# sensors.net
KiCad netlist of a schematic drawn in Altium Designer
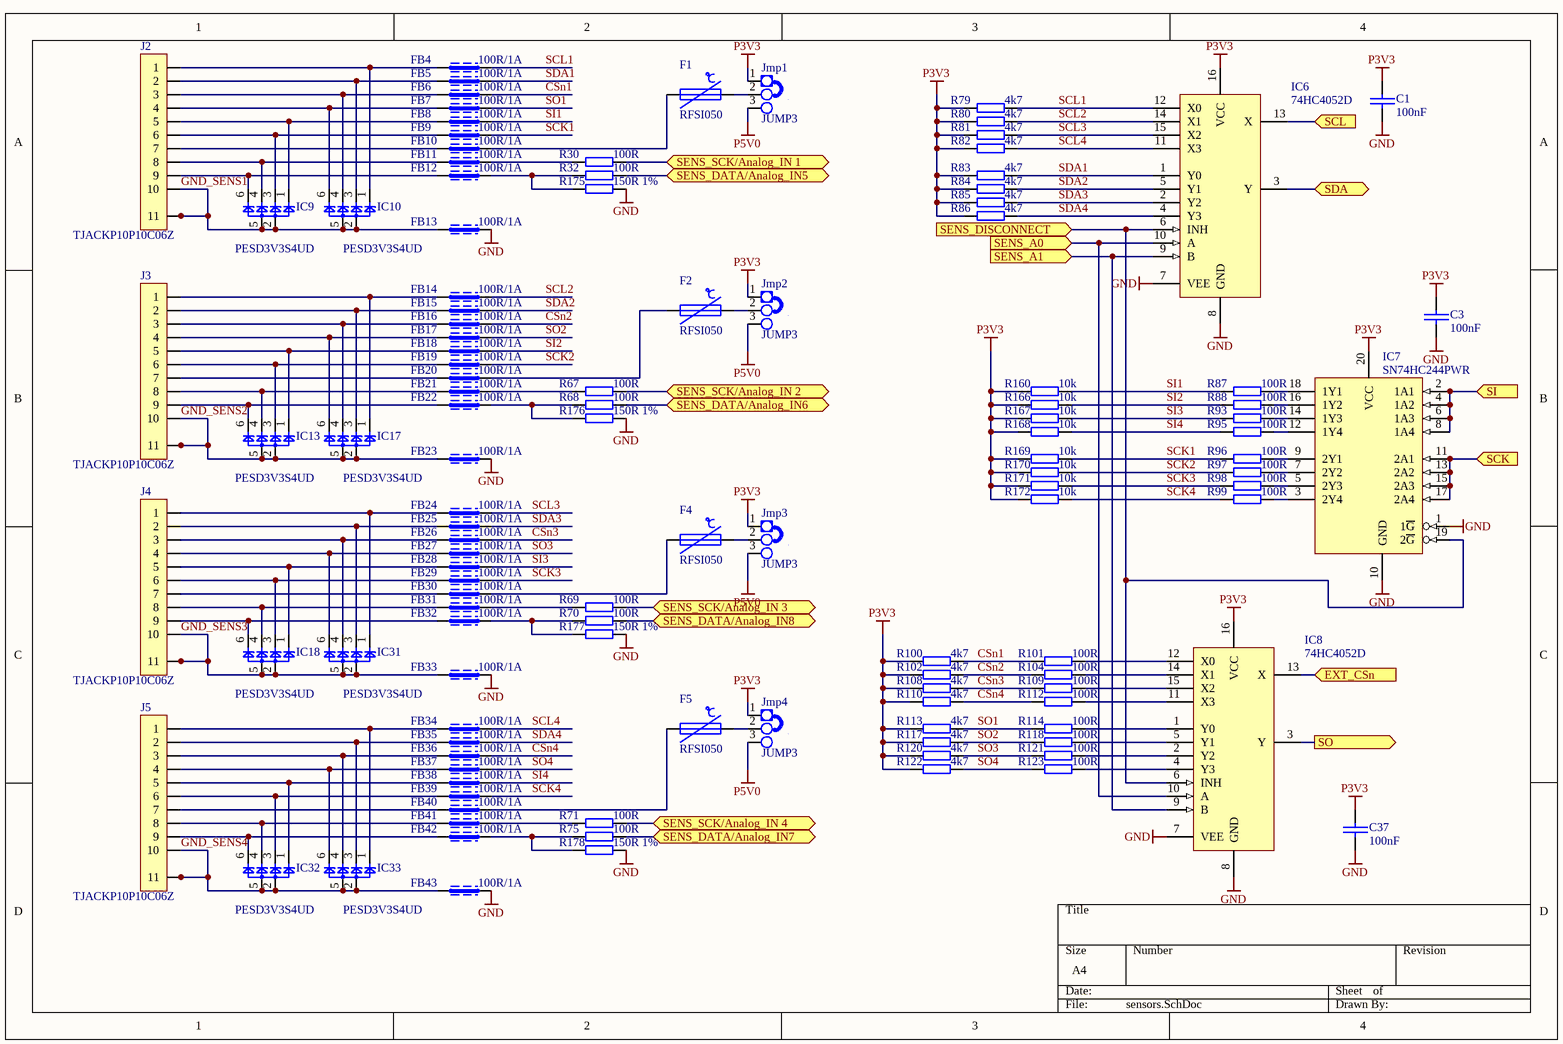
[diagram p0: sensors.SchDoc]

(export (version "E")
  (design (tool "Eeschema 10.0.6"))
  (components
    (comp (ref "C1")
      (value "100nF")
      (footprint "0402C")
      (description "Capacitor SMD")
      (libsource (lib "LIBRARY_SCH") (part "CAP_SMD_0402"))
    )
    (comp (ref "C3")
      (value "100nF")
      (footprint "0402C")
      (description "Capacitor SMD")
      (libsource (lib "LIBRARY_SCH") (part "CAP_SMD_0402"))
    )
    (comp (ref "C37")
      (value "100nF")
      (footprint "0402C")
      (description "Capacitor SMD")
      (libsource (lib "LIBRARY_SCH") (part "CAP_SMD_0402"))
    )
    (comp (ref "F1")
      (value "RFSI050")
      (footprint "0805R")
      (description "50mA polymer FUSE")
      (libsource (lib "LIBRARY_SCH") (part "F_PTC_0.05A"))
    )
    (comp (ref "F2")
      (value "RFSI050")
      (footprint "0805R")
      (description "50mA polymer FUSE")
      (libsource (lib "LIBRARY_SCH") (part "F_PTC_0.05A"))
    )
    (comp (ref "F4")
      (value "RFSI050")
      (footprint "0805R")
      (description "50mA polymer FUSE")
      (libsource (lib "LIBRARY_SCH") (part "F_PTC_0.05A"))
    )
    (comp (ref "F5")
      (value "RFSI050")
      (footprint "0805R")
      (description "50mA polymer FUSE")
      (libsource (lib "LIBRARY_SCH") (part "F_PTC_0.05A"))
    )
    (comp (ref "FB4")
      (value "100R/1A")
      (footprint "0603L")
      (description "ferrite bead 100R@100MHz 1A")
      (libsource (lib "LIBRARY_SCH") (part "L_FERRITE_BEAD_0603"))
    )
    (comp (ref "FB5")
      (value "100R/1A")
      (footprint "0603L")
      (description "ferrite bead 100R@100MHz 1A")
      (libsource (lib "LIBRARY_SCH") (part "L_FERRITE_BEAD_0603"))
    )
    (comp (ref "FB6")
      (value "100R/1A")
      (footprint "0603L")
      (description "ferrite bead 100R@100MHz 1A")
      (libsource (lib "LIBRARY_SCH") (part "L_FERRITE_BEAD_0603"))
    )
    (comp (ref "FB7")
      (value "100R/1A")
      (footprint "0603L")
      (description "ferrite bead 100R@100MHz 1A")
      (libsource (lib "LIBRARY_SCH") (part "L_FERRITE_BEAD_0603"))
    )
    (comp (ref "FB8")
      (value "100R/1A")
      (footprint "0603L")
      (description "ferrite bead 100R@100MHz 1A")
      (libsource (lib "LIBRARY_SCH") (part "L_FERRITE_BEAD_0603"))
    )
    (comp (ref "FB9")
      (value "100R/1A")
      (footprint "0603L")
      (description "ferrite bead 100R@100MHz 1A")
      (libsource (lib "LIBRARY_SCH") (part "L_FERRITE_BEAD_0603"))
    )
    (comp (ref "FB10")
      (value "100R/1A")
      (footprint "0603L")
      (description "ferrite bead 100R@100MHz 1A")
      (libsource (lib "LIBRARY_SCH") (part "L_FERRITE_BEAD_0603"))
    )
    (comp (ref "FB11")
      (value "100R/1A")
      (footprint "0603L")
      (description "ferrite bead 100R@100MHz 1A")
      (libsource (lib "LIBRARY_SCH") (part "L_FERRITE_BEAD_0603"))
    )
    (comp (ref "FB12")
      (value "100R/1A")
      (footprint "0603L")
      (description "ferrite bead 100R@100MHz 1A")
      (libsource (lib "LIBRARY_SCH") (part "L_FERRITE_BEAD_0603"))
    )
    (comp (ref "FB13")
      (value "100R/1A")
      (footprint "0603L")
      (description "ferrite bead 100R@100MHz 1A")
      (libsource (lib "LIBRARY_SCH") (part "L_FERRITE_BEAD_0603"))
    )
    (comp (ref "FB14")
      (value "100R/1A")
      (footprint "0603L")
      (description "ferrite bead 100R@100MHz 1A")
      (libsource (lib "LIBRARY_SCH") (part "L_FERRITE_BEAD_0603"))
    )
    (comp (ref "FB15")
      (value "100R/1A")
      (footprint "0603L")
      (description "ferrite bead 100R@100MHz 1A")
      (libsource (lib "LIBRARY_SCH") (part "L_FERRITE_BEAD_0603"))
    )
    (comp (ref "FB16")
      (value "100R/1A")
      (footprint "0603L")
      (description "ferrite bead 100R@100MHz 1A")
      (libsource (lib "LIBRARY_SCH") (part "L_FERRITE_BEAD_0603"))
    )
    (comp (ref "FB17")
      (value "100R/1A")
      (footprint "0603L")
      (description "ferrite bead 100R@100MHz 1A")
      (libsource (lib "LIBRARY_SCH") (part "L_FERRITE_BEAD_0603"))
    )
    (comp (ref "FB18")
      (value "100R/1A")
      (footprint "0603L")
      (description "ferrite bead 100R@100MHz 1A")
      (libsource (lib "LIBRARY_SCH") (part "L_FERRITE_BEAD_0603"))
    )
    (comp (ref "FB19")
      (value "100R/1A")
      (footprint "0603L")
      (description "ferrite bead 100R@100MHz 1A")
      (libsource (lib "LIBRARY_SCH") (part "L_FERRITE_BEAD_0603"))
    )
    (comp (ref "FB20")
      (value "100R/1A")
      (footprint "0603L")
      (description "ferrite bead 100R@100MHz 1A")
      (libsource (lib "LIBRARY_SCH") (part "L_FERRITE_BEAD_0603"))
    )
    (comp (ref "FB21")
      (value "100R/1A")
      (footprint "0603L")
      (description "ferrite bead 100R@100MHz 1A")
      (libsource (lib "LIBRARY_SCH") (part "L_FERRITE_BEAD_0603"))
    )
    (comp (ref "FB22")
      (value "100R/1A")
      (footprint "0603L")
      (description "ferrite bead 100R@100MHz 1A")
      (libsource (lib "LIBRARY_SCH") (part "L_FERRITE_BEAD_0603"))
    )
    (comp (ref "FB23")
      (value "100R/1A")
      (footprint "0603L")
      (description "ferrite bead 100R@100MHz 1A")
      (libsource (lib "LIBRARY_SCH") (part "L_FERRITE_BEAD_0603"))
    )
    (comp (ref "FB24")
      (value "100R/1A")
      (footprint "0603L")
      (description "ferrite bead 100R@100MHz 1A")
      (libsource (lib "LIBRARY_SCH") (part "L_FERRITE_BEAD_0603"))
    )
    (comp (ref "FB25")
      (value "100R/1A")
      (footprint "0603L")
      (description "ferrite bead 100R@100MHz 1A")
      (libsource (lib "LIBRARY_SCH") (part "L_FERRITE_BEAD_0603"))
    )
    (comp (ref "FB26")
      (value "100R/1A")
      (footprint "0603L")
      (description "ferrite bead 100R@100MHz 1A")
      (libsource (lib "LIBRARY_SCH") (part "L_FERRITE_BEAD_0603"))
    )
    (comp (ref "FB27")
      (value "100R/1A")
      (footprint "0603L")
      (description "ferrite bead 100R@100MHz 1A")
      (libsource (lib "LIBRARY_SCH") (part "L_FERRITE_BEAD_0603"))
    )
    (comp (ref "FB28")
      (value "100R/1A")
      (footprint "0603L")
      (description "ferrite bead 100R@100MHz 1A")
      (libsource (lib "LIBRARY_SCH") (part "L_FERRITE_BEAD_0603"))
    )
    (comp (ref "FB29")
      (value "100R/1A")
      (footprint "0603L")
      (description "ferrite bead 100R@100MHz 1A")
      (libsource (lib "LIBRARY_SCH") (part "L_FERRITE_BEAD_0603"))
    )
    (comp (ref "FB30")
      (value "100R/1A")
      (footprint "0603L")
      (description "ferrite bead 100R@100MHz 1A")
      (libsource (lib "LIBRARY_SCH") (part "L_FERRITE_BEAD_0603"))
    )
    (comp (ref "FB31")
      (value "100R/1A")
      (footprint "0603L")
      (description "ferrite bead 100R@100MHz 1A")
      (libsource (lib "LIBRARY_SCH") (part "L_FERRITE_BEAD_0603"))
    )
    (comp (ref "FB32")
      (value "100R/1A")
      (footprint "0603L")
      (description "ferrite bead 100R@100MHz 1A")
      (libsource (lib "LIBRARY_SCH") (part "L_FERRITE_BEAD_0603"))
    )
    (comp (ref "FB33")
      (value "100R/1A")
      (footprint "0603L")
      (description "ferrite bead 100R@100MHz 1A")
      (libsource (lib "LIBRARY_SCH") (part "L_FERRITE_BEAD_0603"))
    )
    (comp (ref "FB34")
      (value "100R/1A")
      (footprint "0603L")
      (description "ferrite bead 100R@100MHz 1A")
      (libsource (lib "LIBRARY_SCH") (part "L_FERRITE_BEAD_0603"))
    )
    (comp (ref "FB35")
      (value "100R/1A")
      (footprint "0603L")
      (description "ferrite bead 100R@100MHz 1A")
      (libsource (lib "LIBRARY_SCH") (part "L_FERRITE_BEAD_0603"))
    )
    (comp (ref "FB36")
      (value "100R/1A")
      (footprint "0603L")
      (description "ferrite bead 100R@100MHz 1A")
      (libsource (lib "LIBRARY_SCH") (part "L_FERRITE_BEAD_0603"))
    )
    (comp (ref "FB37")
      (value "100R/1A")
      (footprint "0603L")
      (description "ferrite bead 100R@100MHz 1A")
      (libsource (lib "LIBRARY_SCH") (part "L_FERRITE_BEAD_0603"))
    )
    (comp (ref "FB38")
      (value "100R/1A")
      (footprint "0603L")
      (description "ferrite bead 100R@100MHz 1A")
      (libsource (lib "LIBRARY_SCH") (part "L_FERRITE_BEAD_0603"))
    )
    (comp (ref "FB39")
      (value "100R/1A")
      (footprint "0603L")
      (description "ferrite bead 100R@100MHz 1A")
      (libsource (lib "LIBRARY_SCH") (part "L_FERRITE_BEAD_0603"))
    )
    (comp (ref "FB40")
      (value "100R/1A")
      (footprint "0603L")
      (description "ferrite bead 100R@100MHz 1A")
      (libsource (lib "LIBRARY_SCH") (part "L_FERRITE_BEAD_0603"))
    )
    (comp (ref "FB41")
      (value "100R/1A")
      (footprint "0603L")
      (description "ferrite bead 100R@100MHz 1A")
      (libsource (lib "LIBRARY_SCH") (part "L_FERRITE_BEAD_0603"))
    )
    (comp (ref "FB42")
      (value "100R/1A")
      (footprint "0603L")
      (description "ferrite bead 100R@100MHz 1A")
      (libsource (lib "LIBRARY_SCH") (part "L_FERRITE_BEAD_0603"))
    )
    (comp (ref "FB43")
      (value "100R/1A")
      (footprint "0603L")
      (description "ferrite bead 100R@100MHz 1A")
      (libsource (lib "LIBRARY_SCH") (part "L_FERRITE_BEAD_0603"))
    )
    (comp (ref "IC6") (value "74HC4052D") (footprint "SO-16") (libsource (lib "LIBRARY_SCH") (part "4052")))
    (comp (ref "IC7")
      (value "SN74HC244PWR")
      (footprint "tssop20")
      (description "TTL BUS tristate")
      (libsource (lib "LIBRARY_SCH") (part "74HC244"))
    )
    (comp (ref "IC8") (value "74HC4052D") (footprint "SO-16") (libsource (lib "LIBRARY_SCH") (part "4052")))
    (comp (ref "IC9")
      (value "PESD3V3S4UD")
      (footprint "SOT457")
      (description "3.3V TVS")
      (libsource (lib "LIBRARY_SCH") (part "D_TVS_PESD3V3S4UD"))
    )
    (comp (ref "IC10")
      (value "PESD3V3S4UD")
      (footprint "SOT457")
      (description "3.3V TVS")
      (libsource (lib "LIBRARY_SCH") (part "D_TVS_PESD3V3S4UD"))
    )
    (comp (ref "IC13")
      (value "PESD3V3S4UD")
      (footprint "SOT457")
      (description "3.3V TVS")
      (libsource (lib "LIBRARY_SCH") (part "D_TVS_PESD3V3S4UD"))
    )
    (comp (ref "IC17")
      (value "PESD3V3S4UD")
      (footprint "SOT457")
      (description "3.3V TVS")
      (libsource (lib "LIBRARY_SCH") (part "D_TVS_PESD3V3S4UD"))
    )
    (comp (ref "IC18")
      (value "PESD3V3S4UD")
      (footprint "SOT457")
      (description "3.3V TVS")
      (libsource (lib "LIBRARY_SCH") (part "D_TVS_PESD3V3S4UD"))
    )
    (comp (ref "IC31")
      (value "PESD3V3S4UD")
      (footprint "SOT457")
      (description "3.3V TVS")
      (libsource (lib "LIBRARY_SCH") (part "D_TVS_PESD3V3S4UD"))
    )
    (comp (ref "IC32")
      (value "PESD3V3S4UD")
      (footprint "SOT457")
      (description "3.3V TVS")
      (libsource (lib "LIBRARY_SCH") (part "D_TVS_PESD3V3S4UD"))
    )
    (comp (ref "IC33")
      (value "PESD3V3S4UD")
      (footprint "SOT457")
      (description "3.3V TVS")
      (libsource (lib "LIBRARY_SCH") (part "D_TVS_PESD3V3S4UD"))
    )
    (comp (ref "J2")
      (value "TJACKP10P10C06Z")
      (footprint "TJACKP10P10C06Z")
      (description "Modular 10pin (Maritex or Molex)")
      (libsource (lib "LIBRARY_SCH") (part "CON_MOD_10pin_V"))
    )
    (comp (ref "J3")
      (value "TJACKP10P10C06Z")
      (footprint "TJACKP10P10C06Z")
      (description "Modular 10pin (Maritex or Molex)")
      (libsource (lib "LIBRARY_SCH") (part "CON_MOD_10pin_V"))
    )
    (comp (ref "J4")
      (value "TJACKP10P10C06Z")
      (footprint "TJACKP10P10C06Z")
      (description "Modular 10pin (Maritex or Molex)")
      (libsource (lib "LIBRARY_SCH") (part "CON_MOD_10pin_V"))
    )
    (comp (ref "J5")
      (value "TJACKP10P10C06Z")
      (footprint "TJACKP10P10C06Z")
      (description "Modular 10pin (Maritex or Molex)")
      (libsource (lib "LIBRARY_SCH") (part "CON_MOD_10pin_V"))
    )
    (comp (ref "Jmp1") (value "JUMP3") (footprint "jump3") (libsource (lib "LIBRARY_SCH") (part "JUMP3")))
    (comp (ref "Jmp2") (value "JUMP3") (footprint "jump3") (libsource (lib "LIBRARY_SCH") (part "JUMP3")))
    (comp (ref "Jmp3") (value "JUMP3") (footprint "jump3") (libsource (lib "LIBRARY_SCH") (part "JUMP3")))
    (comp (ref "Jmp4") (value "JUMP3") (footprint "jump3") (libsource (lib "LIBRARY_SCH") (part "JUMP3")))
    (comp (ref "R30")
      (value "100R")
      (footprint "0402R")
      (description "SMD Resistor")
      (libsource (lib "LIBRARY_SCH") (part "RES_0402"))
    )
    (comp (ref "R32")
      (value "100R")
      (footprint "0402R")
      (description "SMD Resistor")
      (libsource (lib "LIBRARY_SCH") (part "RES_0402"))
    )
    (comp (ref "R67")
      (value "100R")
      (footprint "0402R")
      (description "SMD Resistor")
      (libsource (lib "LIBRARY_SCH") (part "RES_0402"))
    )
    (comp (ref "R68")
      (value "100R")
      (footprint "0402R")
      (description "SMD Resistor")
      (libsource (lib "LIBRARY_SCH") (part "RES_0402"))
    )
    (comp (ref "R69")
      (value "100R")
      (footprint "0402R")
      (description "SMD Resistor")
      (libsource (lib "LIBRARY_SCH") (part "RES_0402"))
    )
    (comp (ref "R70")
      (value "100R")
      (footprint "0402R")
      (description "SMD Resistor")
      (libsource (lib "LIBRARY_SCH") (part "RES_0402"))
    )
    (comp (ref "R71")
      (value "100R")
      (footprint "0402R")
      (description "SMD Resistor")
      (libsource (lib "LIBRARY_SCH") (part "RES_0402"))
    )
    (comp (ref "R75")
      (value "100R")
      (footprint "0402R")
      (description "SMD Resistor")
      (libsource (lib "LIBRARY_SCH") (part "RES_0402"))
    )
    (comp (ref "R79")
      (value "4k7")
      (footprint "0402R")
      (description "SMD Resistor")
      (libsource (lib "LIBRARY_SCH") (part "RES_0402"))
    )
    (comp (ref "R80")
      (value "4k7")
      (footprint "0402R")
      (description "SMD Resistor")
      (libsource (lib "LIBRARY_SCH") (part "RES_0402"))
    )
    (comp (ref "R81")
      (value "4k7")
      (footprint "0402R")
      (description "SMD Resistor")
      (libsource (lib "LIBRARY_SCH") (part "RES_0402"))
    )
    (comp (ref "R82")
      (value "4k7")
      (footprint "0402R")
      (description "SMD Resistor")
      (libsource (lib "LIBRARY_SCH") (part "RES_0402"))
    )
    (comp (ref "R83")
      (value "4k7")
      (footprint "0402R")
      (description "SMD Resistor")
      (libsource (lib "LIBRARY_SCH") (part "RES_0402"))
    )
    (comp (ref "R84")
      (value "4k7")
      (footprint "0402R")
      (description "SMD Resistor")
      (libsource (lib "LIBRARY_SCH") (part "RES_0402"))
    )
    (comp (ref "R85")
      (value "4k7")
      (footprint "0402R")
      (description "SMD Resistor")
      (libsource (lib "LIBRARY_SCH") (part "RES_0402"))
    )
    (comp (ref "R86")
      (value "4k7")
      (footprint "0402R")
      (description "SMD Resistor")
      (libsource (lib "LIBRARY_SCH") (part "RES_0402"))
    )
    (comp (ref "R87")
      (value "100R")
      (footprint "0402R")
      (description "SMD Resistor")
      (libsource (lib "LIBRARY_SCH") (part "RES_0402"))
    )
    (comp (ref "R88")
      (value "100R")
      (footprint "0402R")
      (description "SMD Resistor")
      (libsource (lib "LIBRARY_SCH") (part "RES_0402"))
    )
    (comp (ref "R93")
      (value "100R")
      (footprint "0402R")
      (description "SMD Resistor")
      (libsource (lib "LIBRARY_SCH") (part "RES_0402"))
    )
    (comp (ref "R95")
      (value "100R")
      (footprint "0402R")
      (description "SMD Resistor")
      (libsource (lib "LIBRARY_SCH") (part "RES_0402"))
    )
    (comp (ref "R96")
      (value "100R")
      (footprint "0402R")
      (description "SMD Resistor")
      (libsource (lib "LIBRARY_SCH") (part "RES_0402"))
    )
    (comp (ref "R97")
      (value "100R")
      (footprint "0402R")
      (description "SMD Resistor")
      (libsource (lib "LIBRARY_SCH") (part "RES_0402"))
    )
    (comp (ref "R98")
      (value "100R")
      (footprint "0402R")
      (description "SMD Resistor")
      (libsource (lib "LIBRARY_SCH") (part "RES_0402"))
    )
    (comp (ref "R99")
      (value "100R")
      (footprint "0402R")
      (description "SMD Resistor")
      (libsource (lib "LIBRARY_SCH") (part "RES_0402"))
    )
    (comp (ref "R100")
      (value "4k7")
      (footprint "0402R")
      (description "SMD Resistor")
      (libsource (lib "LIBRARY_SCH") (part "RES_0402"))
    )
    (comp (ref "R101")
      (value "100R")
      (footprint "0402R")
      (description "SMD Resistor")
      (libsource (lib "LIBRARY_SCH") (part "RES_0402"))
    )
    (comp (ref "R102")
      (value "4k7")
      (footprint "0402R")
      (description "SMD Resistor")
      (libsource (lib "LIBRARY_SCH") (part "RES_0402"))
    )
    (comp (ref "R104")
      (value "100R")
      (footprint "0402R")
      (description "SMD Resistor")
      (libsource (lib "LIBRARY_SCH") (part "RES_0402"))
    )
    (comp (ref "R108")
      (value "4k7")
      (footprint "0402R")
      (description "SMD Resistor")
      (libsource (lib "LIBRARY_SCH") (part "RES_0402"))
    )
    (comp (ref "R109")
      (value "100R")
      (footprint "0402R")
      (description "SMD Resistor")
      (libsource (lib "LIBRARY_SCH") (part "RES_0402"))
    )
    (comp (ref "R110")
      (value "4k7")
      (footprint "0402R")
      (description "SMD Resistor")
      (libsource (lib "LIBRARY_SCH") (part "RES_0402"))
    )
    (comp (ref "R112")
      (value "100R")
      (footprint "0402R")
      (description "SMD Resistor")
      (libsource (lib "LIBRARY_SCH") (part "RES_0402"))
    )
    (comp (ref "R113")
      (value "4k7")
      (footprint "0402R")
      (description "SMD Resistor")
      (libsource (lib "LIBRARY_SCH") (part "RES_0402"))
    )
    (comp (ref "R114")
      (value "100R")
      (footprint "0402R")
      (description "SMD Resistor")
      (libsource (lib "LIBRARY_SCH") (part "RES_0402"))
    )
    (comp (ref "R117")
      (value "4k7")
      (footprint "0402R")
      (description "SMD Resistor")
      (libsource (lib "LIBRARY_SCH") (part "RES_0402"))
    )
    (comp (ref "R118")
      (value "100R")
      (footprint "0402R")
      (description "SMD Resistor")
      (libsource (lib "LIBRARY_SCH") (part "RES_0402"))
    )
    (comp (ref "R120")
      (value "4k7")
      (footprint "0402R")
      (description "SMD Resistor")
      (libsource (lib "LIBRARY_SCH") (part "RES_0402"))
    )
    (comp (ref "R121")
      (value "100R")
      (footprint "0402R")
      (description "SMD Resistor")
      (libsource (lib "LIBRARY_SCH") (part "RES_0402"))
    )
    (comp (ref "R122")
      (value "4k7")
      (footprint "0402R")
      (description "SMD Resistor")
      (libsource (lib "LIBRARY_SCH") (part "RES_0402"))
    )
    (comp (ref "R123")
      (value "100R")
      (footprint "0402R")
      (description "SMD Resistor")
      (libsource (lib "LIBRARY_SCH") (part "RES_0402"))
    )
    (comp (ref "R160")
      (value "10k")
      (footprint "0402R")
      (description "SMD Resistor")
      (libsource (lib "LIBRARY_SCH") (part "RES_0402"))
    )
    (comp (ref "R166")
      (value "10k")
      (footprint "0402R")
      (description "SMD Resistor")
      (libsource (lib "LIBRARY_SCH") (part "RES_0402"))
    )
    (comp (ref "R167")
      (value "10k")
      (footprint "0402R")
      (description "SMD Resistor")
      (libsource (lib "LIBRARY_SCH") (part "RES_0402"))
    )
    (comp (ref "R168")
      (value "10k")
      (footprint "0402R")
      (description "SMD Resistor")
      (libsource (lib "LIBRARY_SCH") (part "RES_0402"))
    )
    (comp (ref "R169")
      (value "10k")
      (footprint "0402R")
      (description "SMD Resistor")
      (libsource (lib "LIBRARY_SCH") (part "RES_0402"))
    )
    (comp (ref "R170")
      (value "10k")
      (footprint "0402R")
      (description "SMD Resistor")
      (libsource (lib "LIBRARY_SCH") (part "RES_0402"))
    )
    (comp (ref "R171")
      (value "10k")
      (footprint "0402R")
      (description "SMD Resistor")
      (libsource (lib "LIBRARY_SCH") (part "RES_0402"))
    )
    (comp (ref "R172")
      (value "10k")
      (footprint "0402R")
      (description "SMD Resistor")
      (libsource (lib "LIBRARY_SCH") (part "RES_0402"))
    )
    (comp (ref "R175")
      (value "150R 1%")
      (footprint "0805R")
      (description "SMD Resistor")
      (libsource (lib "LIBRARY_SCH") (part "RES_0805"))
    )
    (comp (ref "R176")
      (value "150R 1%")
      (footprint "0805R")
      (description "SMD Resistor")
      (libsource (lib "LIBRARY_SCH") (part "RES_0805"))
    )
    (comp (ref "R177")
      (value "150R 1%")
      (footprint "0805R")
      (description "SMD Resistor")
      (libsource (lib "LIBRARY_SCH") (part "RES_0805"))
    )
    (comp (ref "R178")
      (value "150R 1%")
      (footprint "0805R")
      (description "SMD Resistor")
      (libsource (lib "LIBRARY_SCH") (part "RES_0805"))
    )
  )
  (nets
    (net (code "1") (name "/CSn1") (class "Default")
      (node (ref "FB6") (pin "2") (pinfunction "2_2") (pintype "passive"))
      (node (ref "R100") (pin "2") (pinfunction "2_2") (pintype "passive"))
      (node (ref "R101") (pin "1") (pinfunction "1_1") (pintype "passive"))
    )
    (net (code "2") (name "/CSn2") (class "Default")
      (node (ref "FB16") (pin "2") (pinfunction "2_2") (pintype "passive"))
      (node (ref "R102") (pin "2") (pinfunction "2_2") (pintype "passive"))
      (node (ref "R104") (pin "1") (pinfunction "1_1") (pintype "passive"))
    )
    (net (code "3") (name "/CSn3") (class "Default")
      (node (ref "FB26") (pin "2") (pinfunction "2_2") (pintype "passive"))
      (node (ref "R108") (pin "2") (pinfunction "2_2") (pintype "passive"))
      (node (ref "R109") (pin "1") (pinfunction "1_1") (pintype "passive"))
    )
    (net (code "4") (name "/CSn4") (class "Default")
      (node (ref "FB36") (pin "2") (pinfunction "2_2") (pintype "passive"))
      (node (ref "R110") (pin "2") (pinfunction "2_2") (pintype "passive"))
      (node (ref "R112") (pin "1") (pinfunction "1_1") (pintype "passive"))
    )
    (net (code "5") (name "/EXT_CSn") (class "Default")
      (node (ref "IC8") (pin "13") (pinfunction "X_13") (pintype "passive"))
    )
    (net (code "6") (name "/GND_SENS1") (class "Default")
      (node (ref "FB13") (pin "1") (pinfunction "1_1") (pintype "passive"))
      (node (ref "IC10") (pin "2") (pinfunction "2_2") (pintype "passive"))
      (node (ref "IC10") (pin "5") (pinfunction "5_5") (pintype "passive"))
      (node (ref "IC9") (pin "2") (pinfunction "2_2") (pintype "passive"))
      (node (ref "IC9") (pin "5") (pinfunction "5_5") (pintype "passive"))
      (node (ref "J2") (pin "10") (pinfunction "10_10") (pintype "passive"))
      (node (ref "J2") (pin "11") (pinfunction "11_11") (pintype "power_in"))
      (node (ref "J2") (pin "11a") (pinfunction "11_11a") (pintype "power_in"))
      (node (ref "J2") (pin "12") (pinfunction "12_12") (pintype "power_in"))
      (node (ref "J2") (pin "12a") (pinfunction "12_12a") (pintype "power_in"))
    )
    (net (code "7") (name "/GND_SENS2") (class "Default")
      (node (ref "FB23") (pin "1") (pinfunction "1_1") (pintype "passive"))
      (node (ref "IC13") (pin "2") (pinfunction "2_2") (pintype "passive"))
      (node (ref "IC13") (pin "5") (pinfunction "5_5") (pintype "passive"))
      (node (ref "IC17") (pin "2") (pinfunction "2_2") (pintype "passive"))
      (node (ref "IC17") (pin "5") (pinfunction "5_5") (pintype "passive"))
      (node (ref "J3") (pin "10") (pinfunction "10_10") (pintype "passive"))
      (node (ref "J3") (pin "11") (pinfunction "11_11") (pintype "power_in"))
      (node (ref "J3") (pin "11a") (pinfunction "11_11a") (pintype "power_in"))
      (node (ref "J3") (pin "12") (pinfunction "12_12") (pintype "power_in"))
      (node (ref "J3") (pin "12a") (pinfunction "12_12a") (pintype "power_in"))
    )
    (net (code "8") (name "/GND_SENS3") (class "Default")
      (node (ref "FB33") (pin "1") (pinfunction "1_1") (pintype "passive"))
      (node (ref "IC18") (pin "2") (pinfunction "2_2") (pintype "passive"))
      (node (ref "IC18") (pin "5") (pinfunction "5_5") (pintype "passive"))
      (node (ref "IC31") (pin "2") (pinfunction "2_2") (pintype "passive"))
      (node (ref "IC31") (pin "5") (pinfunction "5_5") (pintype "passive"))
      (node (ref "J4") (pin "10") (pinfunction "10_10") (pintype "passive"))
      (node (ref "J4") (pin "11") (pinfunction "11_11") (pintype "power_in"))
      (node (ref "J4") (pin "11a") (pinfunction "11_11a") (pintype "power_in"))
      (node (ref "J4") (pin "12") (pinfunction "12_12") (pintype "power_in"))
      (node (ref "J4") (pin "12a") (pinfunction "12_12a") (pintype "power_in"))
    )
    (net (code "9") (name "/GND_SENS4") (class "Default")
      (node (ref "FB43") (pin "1") (pinfunction "1_1") (pintype "passive"))
      (node (ref "IC32") (pin "2") (pinfunction "2_2") (pintype "passive"))
      (node (ref "IC32") (pin "5") (pinfunction "5_5") (pintype "passive"))
      (node (ref "IC33") (pin "2") (pinfunction "2_2") (pintype "passive"))
      (node (ref "IC33") (pin "5") (pinfunction "5_5") (pintype "passive"))
      (node (ref "J5") (pin "10") (pinfunction "10_10") (pintype "passive"))
      (node (ref "J5") (pin "11") (pinfunction "11_11") (pintype "power_in"))
      (node (ref "J5") (pin "11a") (pinfunction "11_11a") (pintype "power_in"))
      (node (ref "J5") (pin "12") (pinfunction "12_12") (pintype "power_in"))
      (node (ref "J5") (pin "12a") (pinfunction "12_12a") (pintype "power_in"))
    )
    (net (code "10") (name "/SCK") (class "Default")
      (node (ref "IC7") (pin "11") (pinfunction "2A1_11") (pintype "input"))
      (node (ref "IC7") (pin "13") (pinfunction "2A2_13") (pintype "input"))
      (node (ref "IC7") (pin "15") (pinfunction "2A3_15") (pintype "input"))
      (node (ref "IC7") (pin "17") (pinfunction "2A4_17") (pintype "input"))
    )
    (net (code "11") (name "/SCK1") (class "Default")
      (node (ref "FB9") (pin "2") (pinfunction "2_2") (pintype "passive"))
      (node (ref "R169") (pin "2") (pinfunction "2_2") (pintype "passive"))
      (node (ref "R96") (pin "1") (pinfunction "1_1") (pintype "passive"))
    )
    (net (code "12") (name "/SCK2") (class "Default")
      (node (ref "FB19") (pin "2") (pinfunction "2_2") (pintype "passive"))
      (node (ref "R170") (pin "2") (pinfunction "2_2") (pintype "passive"))
      (node (ref "R97") (pin "1") (pinfunction "1_1") (pintype "passive"))
    )
    (net (code "13") (name "/SCK3") (class "Default")
      (node (ref "FB29") (pin "2") (pinfunction "2_2") (pintype "passive"))
      (node (ref "R171") (pin "2") (pinfunction "2_2") (pintype "passive"))
      (node (ref "R98") (pin "1") (pinfunction "1_1") (pintype "passive"))
    )
    (net (code "14") (name "/SCK4") (class "Default")
      (node (ref "FB39") (pin "2") (pinfunction "2_2") (pintype "passive"))
      (node (ref "R172") (pin "2") (pinfunction "2_2") (pintype "passive"))
      (node (ref "R99") (pin "1") (pinfunction "1_1") (pintype "passive"))
    )
    (net (code "15") (name "/SCL") (class "Default")
      (node (ref "IC6") (pin "13") (pinfunction "X_13") (pintype "passive"))
    )
    (net (code "16") (name "/SCL1") (class "Default")
      (node (ref "FB4") (pin "2") (pinfunction "2_2") (pintype "passive"))
      (node (ref "IC6") (pin "12") (pinfunction "X0_12") (pintype "passive"))
      (node (ref "R79") (pin "2") (pinfunction "2_2") (pintype "passive"))
    )
    (net (code "17") (name "/SCL2") (class "Default")
      (node (ref "FB14") (pin "2") (pinfunction "2_2") (pintype "passive"))
      (node (ref "IC6") (pin "14") (pinfunction "X1_14") (pintype "passive"))
      (node (ref "R80") (pin "2") (pinfunction "2_2") (pintype "passive"))
    )
    (net (code "18") (name "/SCL3") (class "Default")
      (node (ref "FB24") (pin "2") (pinfunction "2_2") (pintype "passive"))
      (node (ref "IC6") (pin "15") (pinfunction "X2_15") (pintype "passive"))
      (node (ref "R81") (pin "2") (pinfunction "2_2") (pintype "passive"))
    )
    (net (code "19") (name "/SCL4") (class "Default")
      (node (ref "FB34") (pin "2") (pinfunction "2_2") (pintype "passive"))
      (node (ref "IC6") (pin "11") (pinfunction "X3_11") (pintype "passive"))
      (node (ref "R82") (pin "2") (pinfunction "2_2") (pintype "passive"))
    )
    (net (code "20") (name "/SDA") (class "Default")
      (node (ref "IC6") (pin "3") (pinfunction "Y_3") (pintype "passive"))
    )
    (net (code "21") (name "/SDA1") (class "Default")
      (node (ref "FB5") (pin "2") (pinfunction "2_2") (pintype "passive"))
      (node (ref "IC6") (pin "1") (pinfunction "Y0_1") (pintype "passive"))
      (node (ref "R83") (pin "2") (pinfunction "2_2") (pintype "passive"))
    )
    (net (code "22") (name "/SDA2") (class "Default")
      (node (ref "FB15") (pin "2") (pinfunction "2_2") (pintype "passive"))
      (node (ref "IC6") (pin "5") (pinfunction "Y1_5") (pintype "passive"))
      (node (ref "R84") (pin "2") (pinfunction "2_2") (pintype "passive"))
    )
    (net (code "23") (name "/SDA3") (class "Default")
      (node (ref "FB25") (pin "2") (pinfunction "2_2") (pintype "passive"))
      (node (ref "IC6") (pin "2") (pinfunction "Y2_2") (pintype "passive"))
      (node (ref "R85") (pin "2") (pinfunction "2_2") (pintype "passive"))
    )
    (net (code "24") (name "/SDA4") (class "Default")
      (node (ref "FB35") (pin "2") (pinfunction "2_2") (pintype "passive"))
      (node (ref "IC6") (pin "4") (pinfunction "Y3_4") (pintype "passive"))
      (node (ref "R86") (pin "2") (pinfunction "2_2") (pintype "passive"))
    )
    (net (code "25") (name "/SENS_A0") (class "Default")
      (node (ref "IC6") (pin "10") (pinfunction "A_10") (pintype "input"))
      (node (ref "IC8") (pin "10") (pinfunction "A_10") (pintype "input"))
    )
    (net (code "26") (name "/SENS_A1") (class "Default")
      (node (ref "IC6") (pin "9") (pinfunction "B_9") (pintype "input"))
      (node (ref "IC8") (pin "9") (pinfunction "B_9") (pintype "input"))
    )
    (net (code "27") (name "/SENS_DATA{slash}Analog_IN5") (class "Default")
      (node (ref "R32") (pin "2") (pinfunction "2_2") (pintype "passive"))
    )
    (net (code "28") (name "/SENS_DATA{slash}Analog_IN6") (class "Default")
      (node (ref "R68") (pin "2") (pinfunction "2_2") (pintype "passive"))
    )
    (net (code "29") (name "/SENS_DATA{slash}Analog_IN7") (class "Default")
      (node (ref "R75") (pin "2") (pinfunction "2_2") (pintype "passive"))
    )
    (net (code "30") (name "/SENS_DATA{slash}Analog_IN8") (class "Default")
      (node (ref "R70") (pin "2") (pinfunction "2_2") (pintype "passive"))
    )
    (net (code "31") (name "/SENS_DISCONNECT") (class "Default")
      (node (ref "IC6") (pin "6") (pinfunction "INH_6") (pintype "input"))
      (node (ref "IC7") (pin "19") (pinfunction "2~{G}_19") (pintype "input"))
      (node (ref "IC8") (pin "6") (pinfunction "INH_6") (pintype "input"))
    )
    (net (code "32") (name "/SENS_SCK{slash}Analog_IN 1") (class "Default")
      (node (ref "R30") (pin "2") (pinfunction "2_2") (pintype "passive"))
    )
    (net (code "33") (name "/SENS_SCK{slash}Analog_IN 2") (class "Default")
      (node (ref "R67") (pin "2") (pinfunction "2_2") (pintype "passive"))
    )
    (net (code "34") (name "/SENS_SCK{slash}Analog_IN 3") (class "Default")
      (node (ref "R69") (pin "2") (pinfunction "2_2") (pintype "passive"))
    )
    (net (code "35") (name "/SENS_SCK{slash}Analog_IN 4") (class "Default")
      (node (ref "R71") (pin "2") (pinfunction "2_2") (pintype "passive"))
    )
    (net (code "36") (name "/SI") (class "Default")
      (node (ref "IC7") (pin "2") (pinfunction "1A1_2") (pintype "input"))
      (node (ref "IC7") (pin "4") (pinfunction "1A2_4") (pintype "input"))
      (node (ref "IC7") (pin "6") (pinfunction "1A3_6") (pintype "input"))
      (node (ref "IC7") (pin "8") (pinfunction "1A4_8") (pintype "input"))
    )
    (net (code "37") (name "/SI1") (class "Default")
      (node (ref "FB8") (pin "2") (pinfunction "2_2") (pintype "passive"))
      (node (ref "R160") (pin "2") (pinfunction "2_2") (pintype "passive"))
      (node (ref "R87") (pin "1") (pinfunction "1_1") (pintype "passive"))
    )
    (net (code "38") (name "/SI2") (class "Default")
      (node (ref "FB18") (pin "2") (pinfunction "2_2") (pintype "passive"))
      (node (ref "R166") (pin "2") (pinfunction "2_2") (pintype "passive"))
      (node (ref "R88") (pin "1") (pinfunction "1_1") (pintype "passive"))
    )
    (net (code "39") (name "/SI3") (class "Default")
      (node (ref "FB28") (pin "2") (pinfunction "2_2") (pintype "passive"))
      (node (ref "R167") (pin "2") (pinfunction "2_2") (pintype "passive"))
      (node (ref "R93") (pin "1") (pinfunction "1_1") (pintype "passive"))
    )
    (net (code "40") (name "/SI4") (class "Default")
      (node (ref "FB38") (pin "2") (pinfunction "2_2") (pintype "passive"))
      (node (ref "R168") (pin "2") (pinfunction "2_2") (pintype "passive"))
      (node (ref "R95") (pin "1") (pinfunction "1_1") (pintype "passive"))
    )
    (net (code "41") (name "/SO") (class "Default")
      (node (ref "IC8") (pin "3") (pinfunction "Y_3") (pintype "passive"))
    )
    (net (code "42") (name "/SO1") (class "Default")
      (node (ref "FB7") (pin "2") (pinfunction "2_2") (pintype "passive"))
      (node (ref "R113") (pin "2") (pinfunction "2_2") (pintype "passive"))
      (node (ref "R114") (pin "1") (pinfunction "1_1") (pintype "passive"))
    )
    (net (code "43") (name "/SO2") (class "Default")
      (node (ref "FB17") (pin "2") (pinfunction "2_2") (pintype "passive"))
      (node (ref "R117") (pin "2") (pinfunction "2_2") (pintype "passive"))
      (node (ref "R118") (pin "1") (pinfunction "1_1") (pintype "passive"))
    )
    (net (code "44") (name "/SO3") (class "Default")
      (node (ref "FB27") (pin "2") (pinfunction "2_2") (pintype "passive"))
      (node (ref "R120") (pin "2") (pinfunction "2_2") (pintype "passive"))
      (node (ref "R121") (pin "1") (pinfunction "1_1") (pintype "passive"))
    )
    (net (code "45") (name "/SO4") (class "Default")
      (node (ref "FB37") (pin "2") (pinfunction "2_2") (pintype "passive"))
      (node (ref "R122") (pin "2") (pinfunction "2_2") (pintype "passive"))
      (node (ref "R123") (pin "1") (pinfunction "1_1") (pintype "passive"))
    )
    (net (code "46") (name "GND") (class "Default")
      (node (ref "C1") (pin "2") (pinfunction "2_2") (pintype "passive"))
      (node (ref "C3") (pin "2") (pinfunction "2_2") (pintype "passive"))
      (node (ref "C37") (pin "2") (pinfunction "2_2") (pintype "passive"))
      (node (ref "FB13") (pin "2") (pinfunction "2_2") (pintype "passive"))
      (node (ref "FB23") (pin "2") (pinfunction "2_2") (pintype "passive"))
      (node (ref "FB33") (pin "2") (pinfunction "2_2") (pintype "passive"))
      (node (ref "FB43") (pin "2") (pinfunction "2_2") (pintype "passive"))
      (node (ref "IC6") (pin "7") (pinfunction "VEE_7") (pintype "passive"))
      (node (ref "IC6") (pin "8") (pinfunction "GND_8") (pintype "power_in"))
      (node (ref "IC7") (pin "1") (pinfunction "1~{G}_1") (pintype "input"))
      (node (ref "IC7") (pin "10") (pinfunction "GND_10") (pintype "power_in"))
      (node (ref "IC8") (pin "7") (pinfunction "VEE_7") (pintype "passive"))
      (node (ref "IC8") (pin "8") (pinfunction "GND_8") (pintype "power_in"))
      (node (ref "R175") (pin "2") (pinfunction "2_2") (pintype "passive"))
      (node (ref "R176") (pin "2") (pinfunction "2_2") (pintype "passive"))
      (node (ref "R177") (pin "2") (pinfunction "2_2") (pintype "passive"))
      (node (ref "R178") (pin "2") (pinfunction "2_2") (pintype "passive"))
    )
    (net (code "47") (name "Net-(F1-Pad1)") (class "Default")
      (node (ref "F1") (pin "1") (pinfunction "1_1") (pintype "passive"))
      (node (ref "FB10") (pin "2") (pinfunction "2_2") (pintype "passive"))
    )
    (net (code "48") (name "Net-(F1-Pad2)") (class "Default")
      (node (ref "F1") (pin "2") (pinfunction "2_2") (pintype "passive"))
      (node (ref "Jmp1") (pin "2") (pintype "passive"))
    )
    (net (code "49") (name "Net-(F2-Pad1)") (class "Default")
      (node (ref "F2") (pin "1") (pinfunction "1_1") (pintype "passive"))
      (node (ref "FB20") (pin "2") (pinfunction "2_2") (pintype "passive"))
    )
    (net (code "50") (name "Net-(F2-Pad2)") (class "Default")
      (node (ref "F2") (pin "2") (pinfunction "2_2") (pintype "passive"))
      (node (ref "Jmp2") (pin "2") (pintype "passive"))
    )
    (net (code "51") (name "Net-(F4-Pad1)") (class "Default")
      (node (ref "F4") (pin "1") (pinfunction "1_1") (pintype "passive"))
      (node (ref "FB30") (pin "2") (pinfunction "2_2") (pintype "passive"))
    )
    (net (code "52") (name "Net-(F4-Pad2)") (class "Default")
      (node (ref "F4") (pin "2") (pinfunction "2_2") (pintype "passive"))
      (node (ref "Jmp3") (pin "2") (pintype "passive"))
    )
    (net (code "53") (name "Net-(F5-Pad1)") (class "Default")
      (node (ref "F5") (pin "1") (pinfunction "1_1") (pintype "passive"))
      (node (ref "FB40") (pin "2") (pinfunction "2_2") (pintype "passive"))
    )
    (net (code "54") (name "Net-(F5-Pad2)") (class "Default")
      (node (ref "F5") (pin "2") (pinfunction "2_2") (pintype "passive"))
      (node (ref "Jmp4") (pin "2") (pintype "passive"))
    )
    (net (code "55") (name "Net-(FB4-Pad1)") (class "Default")
      (node (ref "FB4") (pin "1") (pinfunction "1_1") (pintype "passive"))
      (node (ref "IC10") (pin "1") (pinfunction "1_1") (pintype "passive"))
      (node (ref "J2") (pin "1") (pinfunction "1_1") (pintype "passive"))
    )
    (net (code "56") (name "Net-(FB5-Pad1)") (class "Default")
      (node (ref "FB5") (pin "1") (pinfunction "1_1") (pintype "passive"))
      (node (ref "IC10") (pin "3") (pinfunction "3_3") (pintype "passive"))
      (node (ref "J2") (pin "2") (pinfunction "2_2") (pintype "passive"))
    )
    (net (code "57") (name "Net-(FB6-Pad1)") (class "Default")
      (node (ref "FB6") (pin "1") (pinfunction "1_1") (pintype "passive"))
      (node (ref "IC10") (pin "4") (pinfunction "4_4") (pintype "passive"))
      (node (ref "J2") (pin "3") (pinfunction "3_3") (pintype "passive"))
    )
    (net (code "58") (name "Net-(FB7-Pad1)") (class "Default")
      (node (ref "FB7") (pin "1") (pinfunction "1_1") (pintype "passive"))
      (node (ref "IC10") (pin "6") (pinfunction "6_6") (pintype "passive"))
      (node (ref "J2") (pin "4") (pinfunction "4_4") (pintype "passive"))
    )
    (net (code "59") (name "Net-(FB8-Pad1)") (class "Default")
      (node (ref "FB8") (pin "1") (pinfunction "1_1") (pintype "passive"))
      (node (ref "IC9") (pin "1") (pinfunction "1_1") (pintype "passive"))
      (node (ref "J2") (pin "5") (pinfunction "5_5") (pintype "passive"))
    )
    (net (code "60") (name "Net-(FB9-Pad1)") (class "Default")
      (node (ref "FB9") (pin "1") (pinfunction "1_1") (pintype "passive"))
      (node (ref "IC9") (pin "3") (pinfunction "3_3") (pintype "passive"))
      (node (ref "J2") (pin "6") (pinfunction "6_6") (pintype "passive"))
    )
    (net (code "61") (name "Net-(FB10-Pad1)") (class "Default")
      (node (ref "FB10") (pin "1") (pinfunction "1_1") (pintype "passive"))
      (node (ref "J2") (pin "7") (pinfunction "7_7") (pintype "passive"))
    )
    (net (code "62") (name "Net-(FB11-Pad1)") (class "Default")
      (node (ref "FB11") (pin "1") (pinfunction "1_1") (pintype "passive"))
      (node (ref "IC9") (pin "4") (pinfunction "4_4") (pintype "passive"))
      (node (ref "J2") (pin "8") (pinfunction "8_8") (pintype "passive"))
    )
    (net (code "63") (name "Net-(FB11-Pad2)") (class "Default")
      (node (ref "FB11") (pin "2") (pinfunction "2_2") (pintype "passive"))
      (node (ref "R30") (pin "1") (pinfunction "1_1") (pintype "passive"))
    )
    (net (code "64") (name "Net-(FB12-Pad1)") (class "Default")
      (node (ref "FB12") (pin "1") (pinfunction "1_1") (pintype "passive"))
      (node (ref "IC9") (pin "6") (pinfunction "6_6") (pintype "passive"))
      (node (ref "J2") (pin "9") (pinfunction "9_9") (pintype "passive"))
    )
    (net (code "65") (name "Net-(FB12-Pad2)") (class "Default")
      (node (ref "FB12") (pin "2") (pinfunction "2_2") (pintype "passive"))
      (node (ref "R175") (pin "1") (pinfunction "1_1") (pintype "passive"))
      (node (ref "R32") (pin "1") (pinfunction "1_1") (pintype "passive"))
    )
    (net (code "66") (name "Net-(FB14-Pad1)") (class "Default")
      (node (ref "FB14") (pin "1") (pinfunction "1_1") (pintype "passive"))
      (node (ref "IC17") (pin "1") (pinfunction "1_1") (pintype "passive"))
      (node (ref "J3") (pin "1") (pinfunction "1_1") (pintype "passive"))
    )
    (net (code "67") (name "Net-(FB15-Pad1)") (class "Default")
      (node (ref "FB15") (pin "1") (pinfunction "1_1") (pintype "passive"))
      (node (ref "IC17") (pin "3") (pinfunction "3_3") (pintype "passive"))
      (node (ref "J3") (pin "2") (pinfunction "2_2") (pintype "passive"))
    )
    (net (code "68") (name "Net-(FB16-Pad1)") (class "Default")
      (node (ref "FB16") (pin "1") (pinfunction "1_1") (pintype "passive"))
      (node (ref "IC17") (pin "4") (pinfunction "4_4") (pintype "passive"))
      (node (ref "J3") (pin "3") (pinfunction "3_3") (pintype "passive"))
    )
    (net (code "69") (name "Net-(FB17-Pad1)") (class "Default")
      (node (ref "FB17") (pin "1") (pinfunction "1_1") (pintype "passive"))
      (node (ref "IC17") (pin "6") (pinfunction "6_6") (pintype "passive"))
      (node (ref "J3") (pin "4") (pinfunction "4_4") (pintype "passive"))
    )
    (net (code "70") (name "Net-(FB18-Pad1)") (class "Default")
      (node (ref "FB18") (pin "1") (pinfunction "1_1") (pintype "passive"))
      (node (ref "IC13") (pin "1") (pinfunction "1_1") (pintype "passive"))
      (node (ref "J3") (pin "5") (pinfunction "5_5") (pintype "passive"))
    )
    (net (code "71") (name "Net-(FB19-Pad1)") (class "Default")
      (node (ref "FB19") (pin "1") (pinfunction "1_1") (pintype "passive"))
      (node (ref "IC13") (pin "3") (pinfunction "3_3") (pintype "passive"))
      (node (ref "J3") (pin "6") (pinfunction "6_6") (pintype "passive"))
    )
    (net (code "72") (name "Net-(FB20-Pad1)") (class "Default")
      (node (ref "FB20") (pin "1") (pinfunction "1_1") (pintype "passive"))
      (node (ref "J3") (pin "7") (pinfunction "7_7") (pintype "passive"))
    )
    (net (code "73") (name "Net-(FB21-Pad1)") (class "Default")
      (node (ref "FB21") (pin "1") (pinfunction "1_1") (pintype "passive"))
      (node (ref "IC13") (pin "4") (pinfunction "4_4") (pintype "passive"))
      (node (ref "J3") (pin "8") (pinfunction "8_8") (pintype "passive"))
    )
    (net (code "74") (name "Net-(FB21-Pad2)") (class "Default")
      (node (ref "FB21") (pin "2") (pinfunction "2_2") (pintype "passive"))
      (node (ref "R67") (pin "1") (pinfunction "1_1") (pintype "passive"))
    )
    (net (code "75") (name "Net-(FB22-Pad1)") (class "Default")
      (node (ref "FB22") (pin "1") (pinfunction "1_1") (pintype "passive"))
      (node (ref "IC13") (pin "6") (pinfunction "6_6") (pintype "passive"))
      (node (ref "J3") (pin "9") (pinfunction "9_9") (pintype "passive"))
    )
    (net (code "76") (name "Net-(FB22-Pad2)") (class "Default")
      (node (ref "FB22") (pin "2") (pinfunction "2_2") (pintype "passive"))
      (node (ref "R176") (pin "1") (pinfunction "1_1") (pintype "passive"))
      (node (ref "R68") (pin "1") (pinfunction "1_1") (pintype "passive"))
    )
    (net (code "77") (name "Net-(FB24-Pad1)") (class "Default")
      (node (ref "FB24") (pin "1") (pinfunction "1_1") (pintype "passive"))
      (node (ref "IC31") (pin "1") (pinfunction "1_1") (pintype "passive"))
      (node (ref "J4") (pin "1") (pinfunction "1_1") (pintype "passive"))
    )
    (net (code "78") (name "Net-(FB25-Pad1)") (class "Default")
      (node (ref "FB25") (pin "1") (pinfunction "1_1") (pintype "passive"))
      (node (ref "IC31") (pin "3") (pinfunction "3_3") (pintype "passive"))
      (node (ref "J4") (pin "2") (pinfunction "2_2") (pintype "passive"))
    )
    (net (code "79") (name "Net-(FB26-Pad1)") (class "Default")
      (node (ref "FB26") (pin "1") (pinfunction "1_1") (pintype "passive"))
      (node (ref "IC31") (pin "4") (pinfunction "4_4") (pintype "passive"))
      (node (ref "J4") (pin "3") (pinfunction "3_3") (pintype "passive"))
    )
    (net (code "80") (name "Net-(FB27-Pad1)") (class "Default")
      (node (ref "FB27") (pin "1") (pinfunction "1_1") (pintype "passive"))
      (node (ref "IC31") (pin "6") (pinfunction "6_6") (pintype "passive"))
      (node (ref "J4") (pin "4") (pinfunction "4_4") (pintype "passive"))
    )
    (net (code "81") (name "Net-(FB28-Pad1)") (class "Default")
      (node (ref "FB28") (pin "1") (pinfunction "1_1") (pintype "passive"))
      (node (ref "IC18") (pin "1") (pinfunction "1_1") (pintype "passive"))
      (node (ref "J4") (pin "5") (pinfunction "5_5") (pintype "passive"))
    )
    (net (code "82") (name "Net-(FB29-Pad1)") (class "Default")
      (node (ref "FB29") (pin "1") (pinfunction "1_1") (pintype "passive"))
      (node (ref "IC18") (pin "3") (pinfunction "3_3") (pintype "passive"))
      (node (ref "J4") (pin "6") (pinfunction "6_6") (pintype "passive"))
    )
    (net (code "83") (name "Net-(FB30-Pad1)") (class "Default")
      (node (ref "FB30") (pin "1") (pinfunction "1_1") (pintype "passive"))
      (node (ref "J4") (pin "7") (pinfunction "7_7") (pintype "passive"))
    )
    (net (code "84") (name "Net-(FB31-Pad1)") (class "Default")
      (node (ref "FB31") (pin "1") (pinfunction "1_1") (pintype "passive"))
      (node (ref "IC18") (pin "4") (pinfunction "4_4") (pintype "passive"))
      (node (ref "J4") (pin "8") (pinfunction "8_8") (pintype "passive"))
    )
    (net (code "85") (name "Net-(FB31-Pad2)") (class "Default")
      (node (ref "FB31") (pin "2") (pinfunction "2_2") (pintype "passive"))
      (node (ref "R69") (pin "1") (pinfunction "1_1") (pintype "passive"))
    )
    (net (code "86") (name "Net-(FB32-Pad1)") (class "Default")
      (node (ref "FB32") (pin "1") (pinfunction "1_1") (pintype "passive"))
      (node (ref "IC18") (pin "6") (pinfunction "6_6") (pintype "passive"))
      (node (ref "J4") (pin "9") (pinfunction "9_9") (pintype "passive"))
    )
    (net (code "87") (name "Net-(FB32-Pad2)") (class "Default")
      (node (ref "FB32") (pin "2") (pinfunction "2_2") (pintype "passive"))
      (node (ref "R177") (pin "1") (pinfunction "1_1") (pintype "passive"))
      (node (ref "R70") (pin "1") (pinfunction "1_1") (pintype "passive"))
    )
    (net (code "88") (name "Net-(FB34-Pad1)") (class "Default")
      (node (ref "FB34") (pin "1") (pinfunction "1_1") (pintype "passive"))
      (node (ref "IC33") (pin "1") (pinfunction "1_1") (pintype "passive"))
      (node (ref "J5") (pin "1") (pinfunction "1_1") (pintype "passive"))
    )
    (net (code "89") (name "Net-(FB35-Pad1)") (class "Default")
      (node (ref "FB35") (pin "1") (pinfunction "1_1") (pintype "passive"))
      (node (ref "IC33") (pin "3") (pinfunction "3_3") (pintype "passive"))
      (node (ref "J5") (pin "2") (pinfunction "2_2") (pintype "passive"))
    )
    (net (code "90") (name "Net-(FB36-Pad1)") (class "Default")
      (node (ref "FB36") (pin "1") (pinfunction "1_1") (pintype "passive"))
      (node (ref "IC33") (pin "4") (pinfunction "4_4") (pintype "passive"))
      (node (ref "J5") (pin "3") (pinfunction "3_3") (pintype "passive"))
    )
    (net (code "91") (name "Net-(FB37-Pad1)") (class "Default")
      (node (ref "FB37") (pin "1") (pinfunction "1_1") (pintype "passive"))
      (node (ref "IC33") (pin "6") (pinfunction "6_6") (pintype "passive"))
      (node (ref "J5") (pin "4") (pinfunction "4_4") (pintype "passive"))
    )
    (net (code "92") (name "Net-(FB38-Pad1)") (class "Default")
      (node (ref "FB38") (pin "1") (pinfunction "1_1") (pintype "passive"))
      (node (ref "IC32") (pin "1") (pinfunction "1_1") (pintype "passive"))
      (node (ref "J5") (pin "5") (pinfunction "5_5") (pintype "passive"))
    )
    (net (code "93") (name "Net-(FB39-Pad1)") (class "Default")
      (node (ref "FB39") (pin "1") (pinfunction "1_1") (pintype "passive"))
      (node (ref "IC32") (pin "3") (pinfunction "3_3") (pintype "passive"))
      (node (ref "J5") (pin "6") (pinfunction "6_6") (pintype "passive"))
    )
    (net (code "94") (name "Net-(FB40-Pad1)") (class "Default")
      (node (ref "FB40") (pin "1") (pinfunction "1_1") (pintype "passive"))
      (node (ref "J5") (pin "7") (pinfunction "7_7") (pintype "passive"))
    )
    (net (code "95") (name "Net-(FB41-Pad1)") (class "Default")
      (node (ref "FB41") (pin "1") (pinfunction "1_1") (pintype "passive"))
      (node (ref "IC32") (pin "4") (pinfunction "4_4") (pintype "passive"))
      (node (ref "J5") (pin "8") (pinfunction "8_8") (pintype "passive"))
    )
    (net (code "96") (name "Net-(FB41-Pad2)") (class "Default")
      (node (ref "FB41") (pin "2") (pinfunction "2_2") (pintype "passive"))
      (node (ref "R71") (pin "1") (pinfunction "1_1") (pintype "passive"))
    )
    (net (code "97") (name "Net-(FB42-Pad1)") (class "Default")
      (node (ref "FB42") (pin "1") (pinfunction "1_1") (pintype "passive"))
      (node (ref "IC32") (pin "6") (pinfunction "6_6") (pintype "passive"))
      (node (ref "J5") (pin "9") (pinfunction "9_9") (pintype "passive"))
    )
    (net (code "98") (name "Net-(FB42-Pad2)") (class "Default")
      (node (ref "FB42") (pin "2") (pinfunction "2_2") (pintype "passive"))
      (node (ref "R178") (pin "1") (pinfunction "1_1") (pintype "passive"))
      (node (ref "R75") (pin "1") (pinfunction "1_1") (pintype "passive"))
    )
    (net (code "99") (name "Net-(IC7-1Y1)") (class "Default")
      (node (ref "IC7") (pin "18") (pinfunction "1Y1_18") (pintype "tri_state"))
      (node (ref "R87") (pin "2") (pinfunction "2_2") (pintype "passive"))
    )
    (net (code "100") (name "Net-(IC7-1Y2)") (class "Default")
      (node (ref "IC7") (pin "16") (pinfunction "1Y2_16") (pintype "tri_state"))
      (node (ref "R88") (pin "2") (pinfunction "2_2") (pintype "passive"))
    )
    (net (code "101") (name "Net-(IC7-1Y3)") (class "Default")
      (node (ref "IC7") (pin "14") (pinfunction "1Y3_14") (pintype "tri_state"))
      (node (ref "R93") (pin "2") (pinfunction "2_2") (pintype "passive"))
    )
    (net (code "102") (name "Net-(IC7-1Y4)") (class "Default")
      (node (ref "IC7") (pin "12") (pinfunction "1Y4_12") (pintype "tri_state"))
      (node (ref "R95") (pin "2") (pinfunction "2_2") (pintype "passive"))
    )
    (net (code "103") (name "Net-(IC7-2Y1)") (class "Default")
      (node (ref "IC7") (pin "9") (pinfunction "2Y1_9") (pintype "tri_state"))
      (node (ref "R96") (pin "2") (pinfunction "2_2") (pintype "passive"))
    )
    (net (code "104") (name "Net-(IC7-2Y2)") (class "Default")
      (node (ref "IC7") (pin "7") (pinfunction "2Y2_7") (pintype "tri_state"))
      (node (ref "R97") (pin "2") (pinfunction "2_2") (pintype "passive"))
    )
    (net (code "105") (name "Net-(IC7-2Y3)") (class "Default")
      (node (ref "IC7") (pin "5") (pinfunction "2Y3_5") (pintype "tri_state"))
      (node (ref "R98") (pin "2") (pinfunction "2_2") (pintype "passive"))
    )
    (net (code "106") (name "Net-(IC7-2Y4)") (class "Default")
      (node (ref "IC7") (pin "3") (pinfunction "2Y4_3") (pintype "tri_state"))
      (node (ref "R99") (pin "2") (pinfunction "2_2") (pintype "passive"))
    )
    (net (code "107") (name "Net-(IC8-X0)") (class "Default")
      (node (ref "IC8") (pin "12") (pinfunction "X0_12") (pintype "passive"))
      (node (ref "R101") (pin "2") (pinfunction "2_2") (pintype "passive"))
    )
    (net (code "108") (name "Net-(IC8-X1)") (class "Default")
      (node (ref "IC8") (pin "14") (pinfunction "X1_14") (pintype "passive"))
      (node (ref "R104") (pin "2") (pinfunction "2_2") (pintype "passive"))
    )
    (net (code "109") (name "Net-(IC8-X2)") (class "Default")
      (node (ref "IC8") (pin "15") (pinfunction "X2_15") (pintype "passive"))
      (node (ref "R109") (pin "2") (pinfunction "2_2") (pintype "passive"))
    )
    (net (code "110") (name "Net-(IC8-X3)") (class "Default")
      (node (ref "IC8") (pin "11") (pinfunction "X3_11") (pintype "passive"))
      (node (ref "R112") (pin "2") (pinfunction "2_2") (pintype "passive"))
    )
    (net (code "111") (name "Net-(IC8-Y0)") (class "Default")
      (node (ref "IC8") (pin "1") (pinfunction "Y0_1") (pintype "passive"))
      (node (ref "R114") (pin "2") (pinfunction "2_2") (pintype "passive"))
    )
    (net (code "112") (name "Net-(IC8-Y1)") (class "Default")
      (node (ref "IC8") (pin "5") (pinfunction "Y1_5") (pintype "passive"))
      (node (ref "R118") (pin "2") (pinfunction "2_2") (pintype "passive"))
    )
    (net (code "113") (name "Net-(IC8-Y2)") (class "Default")
      (node (ref "IC8") (pin "2") (pinfunction "Y2_2") (pintype "passive"))
      (node (ref "R121") (pin "2") (pinfunction "2_2") (pintype "passive"))
    )
    (net (code "114") (name "Net-(IC8-Y3)") (class "Default")
      (node (ref "IC8") (pin "4") (pinfunction "Y3_4") (pintype "passive"))
      (node (ref "R123") (pin "2") (pinfunction "2_2") (pintype "passive"))
    )
    (net (code "115") (name "P3V3") (class "Default")
      (node (ref "C1") (pin "1") (pinfunction "1_1") (pintype "passive"))
      (node (ref "C3") (pin "1") (pinfunction "1_1") (pintype "passive"))
      (node (ref "C37") (pin "1") (pinfunction "1_1") (pintype "passive"))
      (node (ref "IC6") (pin "16") (pinfunction "VCC_16") (pintype "power_in"))
      (node (ref "IC7") (pin "20") (pinfunction "VCC_20") (pintype "power_in"))
      (node (ref "IC8") (pin "16") (pinfunction "VCC_16") (pintype "power_in"))
      (node (ref "Jmp1") (pin "1") (pintype "passive"))
      (node (ref "Jmp2") (pin "1") (pintype "passive"))
      (node (ref "Jmp3") (pin "1") (pintype "passive"))
      (node (ref "Jmp4") (pin "1") (pintype "passive"))
      (node (ref "R100") (pin "1") (pinfunction "1_1") (pintype "passive"))
      (node (ref "R102") (pin "1") (pinfunction "1_1") (pintype "passive"))
      (node (ref "R108") (pin "1") (pinfunction "1_1") (pintype "passive"))
      (node (ref "R110") (pin "1") (pinfunction "1_1") (pintype "passive"))
      (node (ref "R113") (pin "1") (pinfunction "1_1") (pintype "passive"))
      (node (ref "R117") (pin "1") (pinfunction "1_1") (pintype "passive"))
      (node (ref "R120") (pin "1") (pinfunction "1_1") (pintype "passive"))
      (node (ref "R122") (pin "1") (pinfunction "1_1") (pintype "passive"))
      (node (ref "R160") (pin "1") (pinfunction "1_1") (pintype "passive"))
      (node (ref "R166") (pin "1") (pinfunction "1_1") (pintype "passive"))
      (node (ref "R167") (pin "1") (pinfunction "1_1") (pintype "passive"))
      (node (ref "R168") (pin "1") (pinfunction "1_1") (pintype "passive"))
      (node (ref "R169") (pin "1") (pinfunction "1_1") (pintype "passive"))
      (node (ref "R170") (pin "1") (pinfunction "1_1") (pintype "passive"))
      (node (ref "R171") (pin "1") (pinfunction "1_1") (pintype "passive"))
      (node (ref "R172") (pin "1") (pinfunction "1_1") (pintype "passive"))
      (node (ref "R79") (pin "1") (pinfunction "1_1") (pintype "passive"))
      (node (ref "R80") (pin "1") (pinfunction "1_1") (pintype "passive"))
      (node (ref "R81") (pin "1") (pinfunction "1_1") (pintype "passive"))
      (node (ref "R82") (pin "1") (pinfunction "1_1") (pintype "passive"))
      (node (ref "R83") (pin "1") (pinfunction "1_1") (pintype "passive"))
      (node (ref "R84") (pin "1") (pinfunction "1_1") (pintype "passive"))
      (node (ref "R85") (pin "1") (pinfunction "1_1") (pintype "passive"))
      (node (ref "R86") (pin "1") (pinfunction "1_1") (pintype "passive"))
    )
    (net (code "116") (name "P5V0") (class "Default")
      (node (ref "Jmp1") (pin "3") (pintype "passive"))
      (node (ref "Jmp2") (pin "3") (pintype "passive"))
      (node (ref "Jmp3") (pin "3") (pintype "passive"))
      (node (ref "Jmp4") (pin "3") (pintype "passive"))
    )
  )
)
